# Car_seesaw.net
KiCad netlist of a schematic drawn in Altium Designer
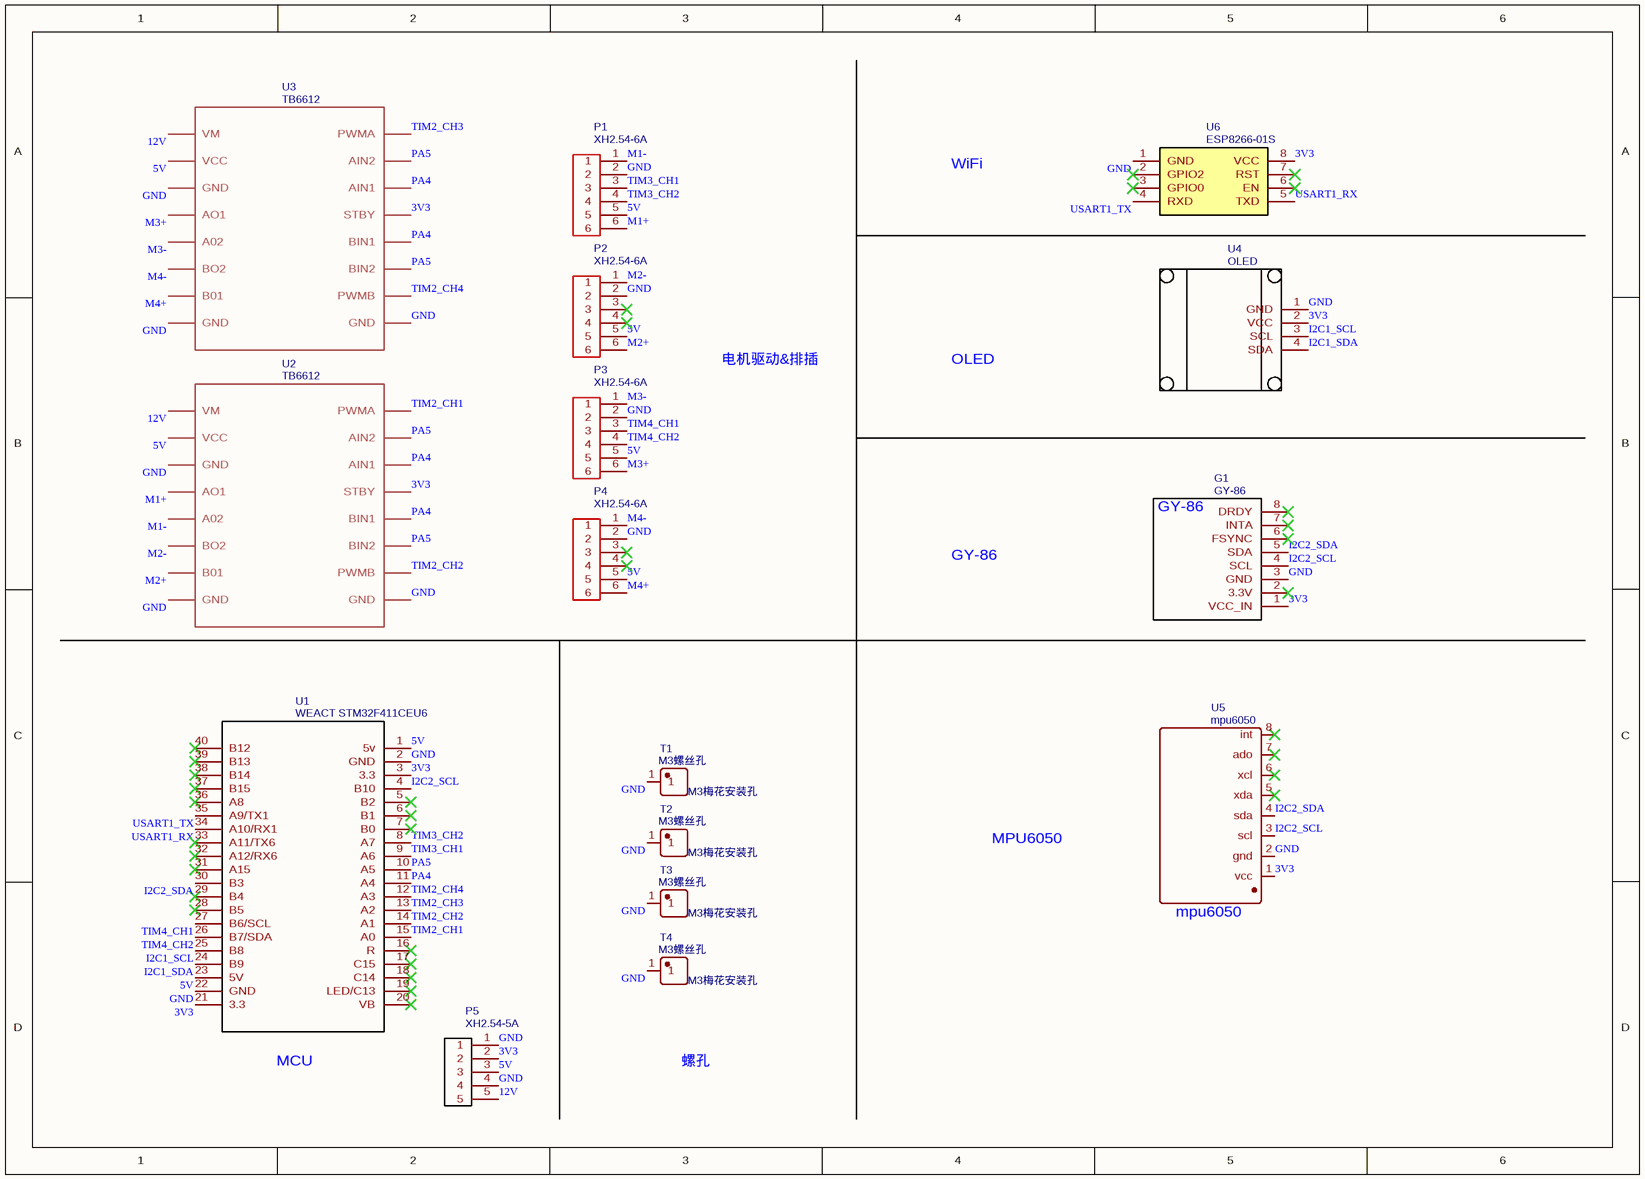
[diagram p0: Car_seesaw.schdoc]

(export (version "E")
  (design (tool "Eeschema 10.0.6"))
  (components
    (comp (ref "G1")
      (value "GY-86")
      (fields (field (name "CONTRIBUTOR") "qianlihaoyue"))
      (libsource (lib "altium-import") (part "root_2_GY-86_"))
    )
    (comp (ref "P1")
      (value "XH2.54-6A")
      (fields (field (name "BOM_SUPPLIER PART") "C33435") (field (name "CONTRIBUTOR") "GESHENG1104"))
      (libsource (lib "altium-import") (part "root_0_XH2.54-6A_"))
    )
    (comp (ref "P2")
      (value "XH2.54-6A")
      (fields (field (name "BOM_SUPPLIER PART") "C33435") (field (name "CONTRIBUTOR") "GESHENG1104"))
      (libsource (lib "altium-import") (part "root_0_XH2.54-6A_"))
    )
    (comp (ref "P3")
      (value "XH2.54-6A")
      (fields (field (name "BOM_SUPPLIER PART") "C33435") (field (name "CONTRIBUTOR") "GESHENG1104"))
      (libsource (lib "altium-import") (part "root_0_XH2.54-6A_"))
    )
    (comp (ref "P4")
      (value "XH2.54-6A")
      (fields (field (name "BOM_SUPPLIER PART") "C33435") (field (name "CONTRIBUTOR") "GESHENG1104"))
      (libsource (lib "altium-import") (part "root_0_XH2.54-6A_"))
    )
    (comp (ref "P5")
      (value "XH2.54-5A")
      (fields
        (field (name "BOM_SUPPLIER PART") "C33435")
        (field (name "BOM_MANUFACTURER PART") "XH2.54-9A")
        (field (name "CONTRIBUTOR") "yds432427")
      )
      (libsource (lib "altium-import") (part "root_0_XH2.54-5A_"))
    )
    (comp (ref "T1")
      (value "M3螺丝孔")
      (fields (field (name "CONTRIBUTOR") "wowlkh"))
      (libsource (lib "altium-import") (part "root_0_M3螺丝孔_"))
    )
    (comp (ref "T2")
      (value "M3螺丝孔")
      (fields (field (name "CONTRIBUTOR") "wowlkh"))
      (libsource (lib "altium-import") (part "root_0_M3螺丝孔_"))
    )
    (comp (ref "T3")
      (value "M3螺丝孔")
      (fields (field (name "CONTRIBUTOR") "wowlkh"))
      (libsource (lib "altium-import") (part "root_0_M3螺丝孔_"))
    )
    (comp (ref "T4")
      (value "M3螺丝孔")
      (fields (field (name "CONTRIBUTOR") "wowlkh"))
      (libsource (lib "altium-import") (part "root_0_M3螺丝孔_"))
    )
    (comp (ref "U1")
      (value "WEACT STM32F411CEU6")
      (fields (field (name "CONTRIBUTOR") "LShang"))
      (libsource (lib "altium-import") (part "root_0_WEACT STM32F411CEU6_"))
    )
    (comp (ref "U2")
      (value "TB6612")
      (fields (field (name "CONTRIBUTOR") "crazyy"))
      (libsource (lib "altium-import") (part "root_0_TB6612_"))
    )
    (comp (ref "U3")
      (value "TB6612")
      (fields (field (name "CONTRIBUTOR") "crazyy"))
      (libsource (lib "altium-import") (part "root_0_TB6612_"))
    )
    (comp (ref "U4")
      (value "OLED")
      (fields
        (field (name "BOM_MANUFACTURER PART") "oled-0.96-4p-i2c")
        (field (name "BOM_SUPPLIER PART") "undefined")
        (field (name "CONTRIBUTOR") "paladina")
      )
      (libsource (lib "altium-import") (part "root_3_OLED_"))
    )
    (comp (ref "U5")
      (value "mpu6050")
      (fields (field (name "CONTRIBUTOR") "nodeb"))
      (libsource (lib "altium-import") (part "root_2_mpu6050_"))
    )
    (comp (ref "U6")
      (value "ESP8266-01S")
      (fields (field (name "CONTRIBUTOR") "selloy521"))
      (libsource (lib "altium-import") (part "root_0_ESP8266-01S_"))
    )
  )
  (nets
    (net (code "1") (name "/3V3") (class "Default")
      (node (ref "G1") (pin "1") (pinfunction "VCC_IN_1") (pintype "passive"))
      (node (ref "P5") (pin "2") (pinfunction "2_2") (pintype "passive"))
      (node (ref "U1") (pin "21") (pinfunction "3.3_21") (pintype "passive"))
      (node (ref "U1") (pin "3") (pinfunction "3.3_3") (pintype "passive"))
      (node (ref "U2") (pin "13") (pinfunction "STBY_13") (pintype "passive"))
      (node (ref "U3") (pin "13") (pinfunction "STBY_13") (pintype "passive"))
      (node (ref "U4") (pin "2") (pinfunction "VCC_2") (pintype "passive"))
      (node (ref "U5") (pin "1") (pinfunction "vcc_1") (pintype "passive"))
      (node (ref "U6") (pin "8") (pinfunction "VCC_8") (pintype "passive"))
    )
    (net (code "2") (name "/5V") (class "Default")
      (node (ref "P1") (pin "5") (pinfunction "5_5") (pintype "passive"))
      (node (ref "P2") (pin "5") (pinfunction "5_5") (pintype "passive"))
      (node (ref "P3") (pin "5") (pinfunction "5_5") (pintype "passive"))
      (node (ref "P4") (pin "5") (pinfunction "5_5") (pintype "passive"))
      (node (ref "P5") (pin "3") (pinfunction "3_3") (pintype "passive"))
      (node (ref "U1") (pin "1") (pinfunction "5v_1") (pintype "passive"))
      (node (ref "U1") (pin "23") (pinfunction "5V_23") (pintype "passive"))
      (node (ref "U2") (pin "2") (pinfunction "VCC_2") (pintype "passive"))
      (node (ref "U3") (pin "2") (pinfunction "VCC_2") (pintype "passive"))
    )
    (net (code "3") (name "/12V") (class "Default")
      (node (ref "P5") (pin "5") (pinfunction "5_5") (pintype "passive"))
      (node (ref "U2") (pin "1") (pinfunction "VM_1") (pintype "passive"))
      (node (ref "U3") (pin "1") (pinfunction "VM_1") (pintype "passive"))
    )
    (net (code "4") (name "/GND") (class "Default")
      (node (ref "G1") (pin "3") (pinfunction "GND_3") (pintype "passive"))
      (node (ref "P1") (pin "2") (pinfunction "2_2") (pintype "passive"))
      (node (ref "P2") (pin "2") (pinfunction "2_2") (pintype "passive"))
      (node (ref "P3") (pin "2") (pinfunction "2_2") (pintype "passive"))
      (node (ref "P4") (pin "2") (pinfunction "2_2") (pintype "passive"))
      (node (ref "P5") (pin "1") (pinfunction "1_1") (pintype "passive"))
      (node (ref "P5") (pin "4") (pinfunction "4_4") (pintype "passive"))
      (node (ref "T1") (pin "1") (pinfunction "1_1") (pintype "passive"))
      (node (ref "T2") (pin "1") (pinfunction "1_1") (pintype "passive"))
      (node (ref "T3") (pin "1") (pinfunction "1_1") (pintype "passive"))
      (node (ref "T4") (pin "1") (pinfunction "1_1") (pintype "passive"))
      (node (ref "U1") (pin "2") (pinfunction "GND_2") (pintype "passive"))
      (node (ref "U1") (pin "22") (pinfunction "GND_22") (pintype "passive"))
      (node (ref "U2") (pin "3") (pinfunction "GND_3") (pintype "passive"))
      (node (ref "U2") (pin "8") (pinfunction "GND_8") (pintype "passive"))
      (node (ref "U2") (pin "9") (pinfunction "GND_9") (pintype "passive"))
      (node (ref "U3") (pin "3") (pinfunction "GND_3") (pintype "passive"))
      (node (ref "U3") (pin "8") (pinfunction "GND_8") (pintype "passive"))
      (node (ref "U3") (pin "9") (pinfunction "GND_9") (pintype "passive"))
      (node (ref "U4") (pin "1") (pinfunction "GND_1") (pintype "passive"))
      (node (ref "U5") (pin "2") (pinfunction "gnd_2") (pintype "passive"))
      (node (ref "U6") (pin "1") (pinfunction "GND_1") (pintype "passive"))
    )
    (net (code "5") (name "/I2C1_SCL") (class "Default")
      (node (ref "U1") (pin "25") (pinfunction "B8_25") (pintype "passive"))
      (node (ref "U4") (pin "3") (pinfunction "SCL_3") (pintype "passive"))
    )
    (net (code "6") (name "/I2C1_SDA") (class "Default")
      (node (ref "U1") (pin "24") (pinfunction "B9_24") (pintype "passive"))
      (node (ref "U4") (pin "4") (pinfunction "SDA_4") (pintype "passive"))
    )
    (net (code "7") (name "/I2C2_SCL") (class "Default")
      (node (ref "G1") (pin "4") (pinfunction "SCL_4") (pintype "passive"))
      (node (ref "U1") (pin "4") (pinfunction "B10_4") (pintype "passive"))
      (node (ref "U5") (pin "3") (pinfunction "scl_3") (pintype "passive"))
    )
    (net (code "8") (name "/I2C2_SDA") (class "Default")
      (node (ref "G1") (pin "5") (pinfunction "SDA_5") (pintype "passive"))
      (node (ref "U1") (pin "30") (pinfunction "B3_30") (pintype "passive"))
      (node (ref "U5") (pin "4") (pinfunction "sda_4") (pintype "passive"))
    )
    (net (code "9") (name "/M1+") (class "Default")
      (node (ref "P1") (pin "6") (pinfunction "6_6") (pintype "passive"))
      (node (ref "U2") (pin "4") (pinfunction "AO1_4") (pintype "passive"))
    )
    (net (code "10") (name "/M1-") (class "Default")
      (node (ref "P1") (pin "1") (pinfunction "1_1") (pintype "passive"))
      (node (ref "U2") (pin "5") (pinfunction "A02_5") (pintype "passive"))
    )
    (net (code "11") (name "/M2+") (class "Default")
      (node (ref "P2") (pin "6") (pinfunction "6_6") (pintype "passive"))
      (node (ref "U2") (pin "7") (pinfunction "B01_7") (pintype "passive"))
    )
    (net (code "12") (name "/M2-") (class "Default")
      (node (ref "P2") (pin "1") (pinfunction "1_1") (pintype "passive"))
      (node (ref "U2") (pin "6") (pinfunction "BO2_6") (pintype "passive"))
    )
    (net (code "13") (name "/M3+") (class "Default")
      (node (ref "P3") (pin "6") (pinfunction "6_6") (pintype "passive"))
      (node (ref "U3") (pin "4") (pinfunction "AO1_4") (pintype "passive"))
    )
    (net (code "14") (name "/M3-") (class "Default")
      (node (ref "P3") (pin "1") (pinfunction "1_1") (pintype "passive"))
      (node (ref "U3") (pin "5") (pinfunction "A02_5") (pintype "passive"))
    )
    (net (code "15") (name "/M4+") (class "Default")
      (node (ref "P4") (pin "6") (pinfunction "6_6") (pintype "passive"))
      (node (ref "U3") (pin "7") (pinfunction "B01_7") (pintype "passive"))
    )
    (net (code "16") (name "/M4-") (class "Default")
      (node (ref "P4") (pin "1") (pinfunction "1_1") (pintype "passive"))
      (node (ref "U3") (pin "6") (pinfunction "BO2_6") (pintype "passive"))
    )
    (net (code "17") (name "/PA4") (class "Default")
      (node (ref "U1") (pin "11") (pinfunction "A4_11") (pintype "passive"))
      (node (ref "U2") (pin "12") (pinfunction "BIN1_12") (pintype "passive"))
      (node (ref "U2") (pin "14") (pinfunction "AIN1_14") (pintype "passive"))
      (node (ref "U3") (pin "12") (pinfunction "BIN1_12") (pintype "passive"))
      (node (ref "U3") (pin "14") (pinfunction "AIN1_14") (pintype "passive"))
    )
    (net (code "18") (name "/PA5") (class "Default")
      (node (ref "U1") (pin "10") (pinfunction "A5_10") (pintype "passive"))
      (node (ref "U2") (pin "11") (pinfunction "BIN2_11") (pintype "passive"))
      (node (ref "U2") (pin "15") (pinfunction "AIN2_15") (pintype "passive"))
      (node (ref "U3") (pin "11") (pinfunction "BIN2_11") (pintype "passive"))
      (node (ref "U3") (pin "15") (pinfunction "AIN2_15") (pintype "passive"))
    )
    (net (code "19") (name "/TIM2_CH1") (class "Default")
      (node (ref "U1") (pin "15") (pinfunction "A0_15") (pintype "passive"))
      (node (ref "U2") (pin "16") (pinfunction "PWMA_16") (pintype "passive"))
    )
    (net (code "20") (name "/TIM2_CH2") (class "Default")
      (node (ref "U1") (pin "14") (pinfunction "A1_14") (pintype "passive"))
      (node (ref "U2") (pin "10") (pinfunction "PWMB_10") (pintype "passive"))
    )
    (net (code "21") (name "/TIM2_CH3") (class "Default")
      (node (ref "U1") (pin "13") (pinfunction "A2_13") (pintype "passive"))
      (node (ref "U3") (pin "16") (pinfunction "PWMA_16") (pintype "passive"))
    )
    (net (code "22") (name "/TIM2_CH4") (class "Default")
      (node (ref "U1") (pin "12") (pinfunction "A3_12") (pintype "passive"))
      (node (ref "U3") (pin "10") (pinfunction "PWMB_10") (pintype "passive"))
    )
    (net (code "23") (name "/TIM3_CH1") (class "Default")
      (node (ref "P1") (pin "3") (pinfunction "3_3") (pintype "passive"))
      (node (ref "U1") (pin "9") (pinfunction "A6_9") (pintype "passive"))
    )
    (net (code "24") (name "/TIM3_CH2") (class "Default")
      (node (ref "P1") (pin "4") (pinfunction "4_4") (pintype "passive"))
      (node (ref "U1") (pin "8") (pinfunction "A7_8") (pintype "passive"))
    )
    (net (code "25") (name "/TIM4_CH1") (class "Default")
      (node (ref "P3") (pin "3") (pinfunction "3_3") (pintype "passive"))
      (node (ref "U1") (pin "27") (pinfunction "B6/SCL_27") (pintype "passive"))
    )
    (net (code "26") (name "/TIM4_CH2") (class "Default")
      (node (ref "P3") (pin "4") (pinfunction "4_4") (pintype "passive"))
      (node (ref "U1") (pin "26") (pinfunction "B7/SDA_26") (pintype "passive"))
    )
    (net (code "27") (name "/USART1_RX") (class "Default")
      (node (ref "U1") (pin "34") (pinfunction "A10/RX1_34") (pintype "passive"))
      (node (ref "U6") (pin "5") (pinfunction "TXD_5") (pintype "passive"))
    )
    (net (code "28") (name "/USART1_TX") (class "Default")
      (node (ref "U1") (pin "35") (pinfunction "A9/TX1_35") (pintype "passive"))
      (node (ref "U6") (pin "4") (pinfunction "RXD_4") (pintype "passive"))
    )
    (net (code "29") (name "unconnected-(G1-3.3V-Pad2)") (class "Default")
      (node (ref "G1") (pin "2") (pinfunction "3.3V_2") (pintype "passive+no_connect"))
    )
    (net (code "30") (name "unconnected-(G1-DRDY-Pad8)") (class "Default")
      (node (ref "G1") (pin "8") (pinfunction "DRDY_8") (pintype "passive+no_connect"))
    )
    (net (code "31") (name "unconnected-(G1-FSYNC-Pad6)") (class "Default")
      (node (ref "G1") (pin "6") (pinfunction "FSYNC_6") (pintype "passive+no_connect"))
    )
    (net (code "32") (name "unconnected-(G1-INTA-Pad7)") (class "Default")
      (node (ref "G1") (pin "7") (pinfunction "INTA_7") (pintype "passive+no_connect"))
    )
    (net (code "33") (name "unconnected-(P2-Pad3)") (class "Default")
      (node (ref "P2") (pin "3") (pinfunction "3_3") (pintype "passive+no_connect"))
    )
    (net (code "34") (name "unconnected-(P2-Pad4)") (class "Default")
      (node (ref "P2") (pin "4") (pinfunction "4_4") (pintype "passive+no_connect"))
    )
    (net (code "35") (name "unconnected-(P4-Pad3)") (class "Default")
      (node (ref "P4") (pin "3") (pinfunction "3_3") (pintype "passive+no_connect"))
    )
    (net (code "36") (name "unconnected-(P4-Pad4)") (class "Default")
      (node (ref "P4") (pin "4") (pinfunction "4_4") (pintype "passive+no_connect"))
    )
    (net (code "37") (name "unconnected-(U1-A8-Pad36)") (class "Default")
      (node (ref "U1") (pin "36") (pinfunction "A8_36") (pintype "passive+no_connect"))
    )
    (net (code "38") (name "unconnected-(U1-A11{slash}TX6-Pad33)") (class "Default")
      (node (ref "U1") (pin "33") (pinfunction "A11/TX6_33") (pintype "passive+no_connect"))
    )
    (net (code "39") (name "unconnected-(U1-A12{slash}RX6-Pad32)") (class "Default")
      (node (ref "U1") (pin "32") (pinfunction "A12/RX6_32") (pintype "passive+no_connect"))
    )
    (net (code "40") (name "unconnected-(U1-A15-Pad31)") (class "Default")
      (node (ref "U1") (pin "31") (pinfunction "A15_31") (pintype "passive+no_connect"))
    )
    (net (code "41") (name "unconnected-(U1-B0-Pad7)") (class "Default")
      (node (ref "U1") (pin "7") (pinfunction "B0_7") (pintype "passive+no_connect"))
    )
    (net (code "42") (name "unconnected-(U1-B1-Pad6)") (class "Default")
      (node (ref "U1") (pin "6") (pinfunction "B1_6") (pintype "passive+no_connect"))
    )
    (net (code "43") (name "unconnected-(U1-B2-Pad5)") (class "Default")
      (node (ref "U1") (pin "5") (pinfunction "B2_5") (pintype "passive+no_connect"))
    )
    (net (code "44") (name "unconnected-(U1-B4-Pad29)") (class "Default")
      (node (ref "U1") (pin "29") (pinfunction "B4_29") (pintype "passive+no_connect"))
    )
    (net (code "45") (name "unconnected-(U1-B5-Pad28)") (class "Default")
      (node (ref "U1") (pin "28") (pinfunction "B5_28") (pintype "passive+no_connect"))
    )
    (net (code "46") (name "unconnected-(U1-B12-Pad40)") (class "Default")
      (node (ref "U1") (pin "40") (pinfunction "B12_40") (pintype "passive+no_connect"))
    )
    (net (code "47") (name "unconnected-(U1-B13-Pad39)") (class "Default")
      (node (ref "U1") (pin "39") (pinfunction "B13_39") (pintype "passive+no_connect"))
    )
    (net (code "48") (name "unconnected-(U1-B14-Pad38)") (class "Default")
      (node (ref "U1") (pin "38") (pinfunction "B14_38") (pintype "passive+no_connect"))
    )
    (net (code "49") (name "unconnected-(U1-B15-Pad37)") (class "Default")
      (node (ref "U1") (pin "37") (pinfunction "B15_37") (pintype "passive+no_connect"))
    )
    (net (code "50") (name "unconnected-(U1-C14-Pad18)") (class "Default")
      (node (ref "U1") (pin "18") (pinfunction "C14_18") (pintype "passive+no_connect"))
    )
    (net (code "51") (name "unconnected-(U1-C15-Pad17)") (class "Default")
      (node (ref "U1") (pin "17") (pinfunction "C15_17") (pintype "passive+no_connect"))
    )
    (net (code "52") (name "unconnected-(U1-LED{slash}C13-Pad19)") (class "Default")
      (node (ref "U1") (pin "19") (pinfunction "LED/C13_19") (pintype "passive+no_connect"))
    )
    (net (code "53") (name "unconnected-(U1-R-Pad16)") (class "Default")
      (node (ref "U1") (pin "16") (pinfunction "R_16") (pintype "passive+no_connect"))
    )
    (net (code "54") (name "unconnected-(U1-VB-Pad20)") (class "Default")
      (node (ref "U1") (pin "20") (pinfunction "VB_20") (pintype "passive+no_connect"))
    )
    (net (code "55") (name "unconnected-(U5-ado-Pad7)") (class "Default")
      (node (ref "U5") (pin "7") (pinfunction "ado_7") (pintype "passive+no_connect"))
    )
    (net (code "56") (name "unconnected-(U5-int-Pad8)") (class "Default")
      (node (ref "U5") (pin "8") (pinfunction "int_8") (pintype "passive+no_connect"))
    )
    (net (code "57") (name "unconnected-(U5-xcl-Pad6)") (class "Default")
      (node (ref "U5") (pin "6") (pinfunction "xcl_6") (pintype "passive+no_connect"))
    )
    (net (code "58") (name "unconnected-(U5-xda-Pad5)") (class "Default")
      (node (ref "U5") (pin "5") (pinfunction "xda_5") (pintype "passive+no_connect"))
    )
    (net (code "59") (name "unconnected-(U6-EN-Pad6)") (class "Default")
      (node (ref "U6") (pin "6") (pinfunction "EN_6") (pintype "passive+no_connect"))
    )
    (net (code "60") (name "unconnected-(U6-GPIO0-Pad3)") (class "Default")
      (node (ref "U6") (pin "3") (pinfunction "GPIO0_3") (pintype "passive+no_connect"))
    )
    (net (code "61") (name "unconnected-(U6-GPIO2-Pad2)") (class "Default")
      (node (ref "U6") (pin "2") (pinfunction "GPIO2_2") (pintype "passive+no_connect"))
    )
    (net (code "62") (name "unconnected-(U6-RST-Pad7)") (class "Default")
      (node (ref "U6") (pin "7") (pinfunction "RST_7") (pintype "passive+no_connect"))
    )
  )
)
